# ADL5545WideBandAmp.net
KiCad netlist of a schematic drawn in Altium Designer
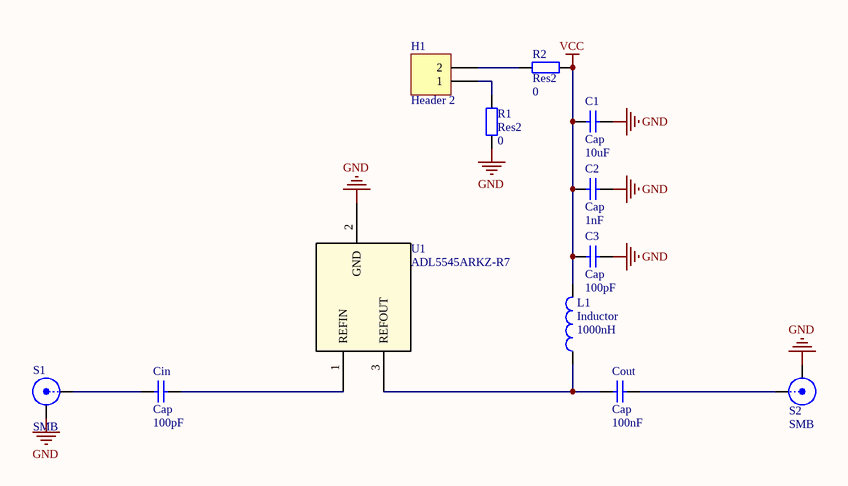
[diagram p0: ADL5545WideBandAmp.SchDoc]

(export (version "E")
  (design (tool "Eeschema 10.0.6"))
  (components
    (comp (ref "C1")
      (value "Cap")
      (footprint "CAP_SMD_3216")
      (description "Capacitor")
      (fields (field (name "ALTIUM_VALUE") "10uF") (field (name "PUBLISHER") "Altium Limited"))
      (libsource (lib "Miscellaneous Devices") (part "Cap"))
    )
    (comp (ref "C2")
      (value "Cap")
      (footprint "0805C")
      (description "Capacitor")
      (fields (field (name "ALTIUM_VALUE") "1nF") (field (name "PUBLISHER") "Altium Limited"))
      (libsource (lib "Miscellaneous Devices") (part "Cap"))
    )
    (comp (ref "C3")
      (value "Cap")
      (footprint "0805C")
      (description "Capacitor")
      (fields (field (name "ALTIUM_VALUE") "100pF") (field (name "PUBLISHER") "Altium Limited"))
      (libsource (lib "Miscellaneous Devices") (part "Cap"))
    )
    (comp (ref "Cin")
      (value "Cap")
      (footprint "0805C")
      (description "Capacitor")
      (fields (field (name "ALTIUM_VALUE") "100pF") (field (name "PUBLISHER") "Altium Limited"))
      (libsource (lib "Miscellaneous Devices") (part "Cap"))
    )
    (comp (ref "Cout")
      (value "Cap")
      (footprint "0805C")
      (description "Capacitor")
      (fields (field (name "ALTIUM_VALUE") "100nF") (field (name "PUBLISHER") "Altium Limited"))
      (libsource (lib "Miscellaneous Devices") (part "Cap"))
    )
    (comp (ref "H1")
      (value "Header 2")
      (footprint "HDR1X2")
      (description "Header, 2-Pin")
      (fields (field (name "PUBLISHER") "Altium Limited"))
      (libsource (lib "Miscellaneous Connectors") (part "Header 2"))
    )
    (comp (ref "L1")
      (value "Inductor")
      (footprint "0805L")
      (fields (field (name "ALTIUM_VALUE") "1000nH") (field (name "PUBLISHER") "Altium Limited"))
      (libsource (lib "Miscellaneous Devices") (part "Inductor"))
    )
    (comp (ref "R1")
      (value "Res2")
      (footprint "AXIAL-0.4")
      (description "Resistor")
      (fields (field (name "ALTIUM_VALUE") "0") (field (name "PUBLISHER") "Altium Limited"))
      (libsource (lib "") (part "Res2_1"))
    )
    (comp (ref "R2")
      (value "Res2")
      (footprint "AXIAL-0.4")
      (description "Resistor")
      (fields (field (name "ALTIUM_VALUE") "0") (field (name "PUBLISHER") "Altium Limited"))
      (libsource (lib "Miscellaneous Devices") (part "Res2"))
    )
    (comp (ref "S1")
      (value "SMB")
      (footprint "SMB_V-RJ45")
      (description "SMB Straight Connector")
      (fields (field (name "PUBLISHER") "Altium Limited"))
      (libsource (lib "Miscellaneous Connectors") (part "SMB"))
    )
    (comp (ref "S2")
      (value "SMB")
      (footprint "SMB_V-RJ45")
      (description "SMB Straight Connector")
      (fields (field (name "PUBLISHER") "Altium Limited"))
      (libsource (lib "Miscellaneous Connectors") (part "SMB"))
    )
    (comp (ref "U1")
      (value "ADL5545ARKZ-R7")
      (footprint "RK_3")
      (description "Imported")
      (libsource (lib "ADL5545ARKZ-R7") (part "ADL5545ARKZ-R7"))
    )
  )
  (nets
    (net (code "1") (name "GND") (class "Default")
      (node (ref "C1") (pin "2") (pinfunction "2_2") (pintype "passive"))
      (node (ref "C2") (pin "2") (pinfunction "2_2") (pintype "passive"))
      (node (ref "C3") (pin "2") (pinfunction "2_2") (pintype "passive"))
      (node (ref "R1") (pin "2") (pinfunction "2_2") (pintype "passive"))
      (node (ref "S1") (pin "2") (pinfunction "Y_2") (pintype "passive"))
      (node (ref "S2") (pin "2") (pinfunction "Y_2") (pintype "passive"))
      (node (ref "U1") (pin "2") (pinfunction "GND_2") (pintype "passive"))
    )
    (net (code "2") (name "Net-(H1-Pad1)") (class "Default")
      (node (ref "H1") (pin "1") (pinfunction "1_1") (pintype "passive"))
      (node (ref "R1") (pin "1") (pinfunction "1_1") (pintype "passive"))
    )
    (net (code "3") (name "Net-(H1-Pad2)") (class "Default")
      (node (ref "H1") (pin "2") (pinfunction "2_2") (pintype "passive"))
      (node (ref "R2") (pin "1") (pinfunction "1_1") (pintype "passive"))
    )
    (net (code "4") (name "Net-(S1-X)") (class "Default")
      (node (ref "Cin") (pin "1") (pinfunction "1_1") (pintype "passive"))
      (node (ref "S1") (pin "1") (pinfunction "X_1") (pintype "passive"))
    )
    (net (code "5") (name "Net-(S2-X)") (class "Default")
      (node (ref "Cout") (pin "2") (pinfunction "2_2") (pintype "passive"))
      (node (ref "S2") (pin "1") (pinfunction "X_1") (pintype "passive"))
    )
    (net (code "6") (name "Net-(U1-REFIN)") (class "Default")
      (node (ref "Cin") (pin "2") (pinfunction "2_2") (pintype "passive"))
      (node (ref "U1") (pin "1") (pinfunction "REFIN_1") (pintype "passive"))
    )
    (net (code "7") (name "Net-(U1-REFOUT)") (class "Default")
      (node (ref "Cout") (pin "1") (pinfunction "1_1") (pintype "passive"))
      (node (ref "L1") (pin "1") (pinfunction "1_1") (pintype "passive"))
      (node (ref "U1") (pin "3") (pinfunction "REFOUT_3") (pintype "passive"))
    )
    (net (code "8") (name "VCC") (class "Default")
      (node (ref "C1") (pin "1") (pinfunction "1_1") (pintype "passive"))
      (node (ref "C2") (pin "1") (pinfunction "1_1") (pintype "passive"))
      (node (ref "C3") (pin "1") (pinfunction "1_1") (pintype "passive"))
      (node (ref "L1") (pin "2") (pinfunction "2_2") (pintype "passive"))
      (node (ref "R2") (pin "2") (pinfunction "2_2") (pintype "passive"))
    )
  )
)
